# ArduinoNano_LearningBot_5-14-18.net
KiCad netlist of a schematic drawn in EAGLE
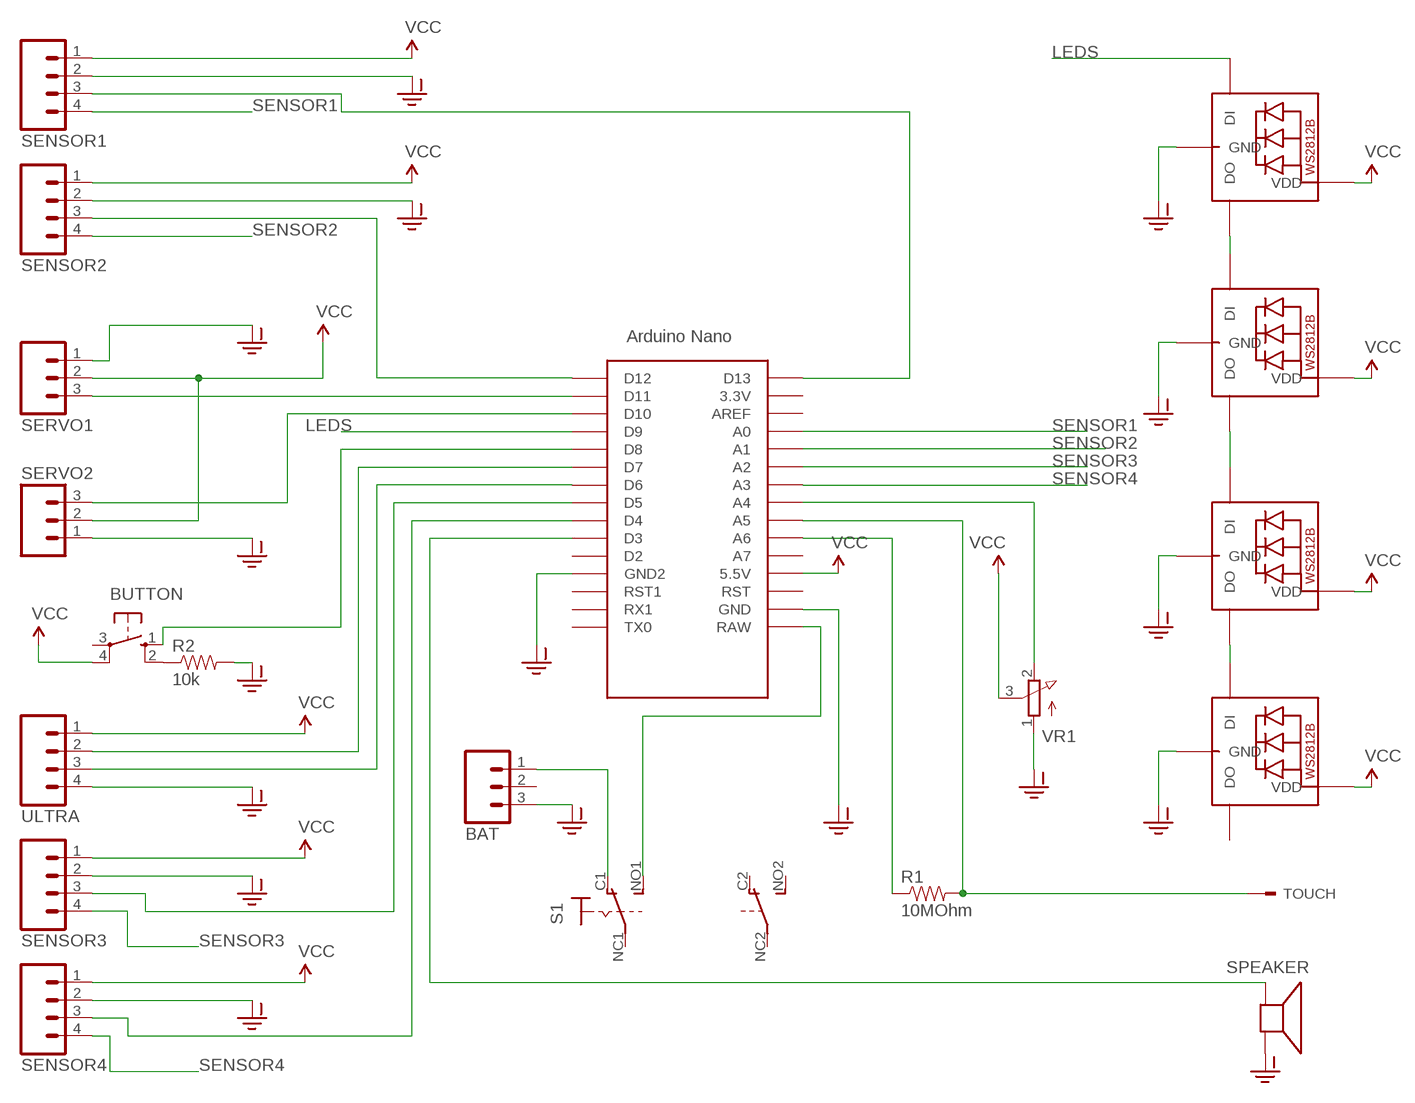
[diagram p0: schematic, sheet 1]

(export (version "E")
  (design (tool "Eeschema 10.0.6"))
  (components
    (comp (ref "BAT")
      (value "M03POLAR")
      (footprint "eagle-import:MOLEX-1X3")
      (libsource (lib "eagle-import") (part "M03POLAR"))
    )
    (comp (ref "BUTTON")
      (value "10-XX")
      (footprint "eagle-import:B3F-10XX")
      (fields (field (name "MPN") "B3F-1000"))
      (libsource (lib "eagle-import") (part "10-XX"))
    )
    (comp (ref "LED1")
      (value "WS2812B5050")
      (footprint "eagle-import:WS2812B")
      (libsource (lib "eagle-import") (part "WS2812B5050"))
    )
    (comp (ref "LED2")
      (value "WS2812B5050")
      (footprint "eagle-import:WS2812B")
      (libsource (lib "eagle-import") (part "WS2812B5050"))
    )
    (comp (ref "LED3")
      (value "WS2812B5050")
      (footprint "eagle-import:WS2812B")
      (libsource (lib "eagle-import") (part "WS2812B5050"))
    )
    (comp (ref "LED4")
      (value "WS2812B5050")
      (footprint "eagle-import:WS2812B")
      (libsource (lib "eagle-import") (part "WS2812B5050"))
    )
    (comp (ref "R1")
      (value "10MOhm")
      (footprint "eagle-import:AXIAL-0.4")
      (libsource (lib "eagle-import") (part "RESISTORPTH-1/4W"))
    )
    (comp (ref "R2")
      (value "10k")
      (footprint "eagle-import:AXIAL-0.4")
      (libsource (lib "eagle-import") (part "RESISTORPTH-1/4W"))
    )
    (comp (ref "S1")
      (value "SWITCH_320-938")
      (footprint "eagle-import:PS22F03")
      (libsource (lib "eagle-import") (part "SWITCH_320-938"))
    )
    (comp (ref "SENSOR1")
      (value "M04LOCK")
      (footprint "eagle-import:1X04_LOCK")
      (libsource (lib "eagle-import") (part "M04LOCK"))
    )
    (comp (ref "SENSOR2")
      (value "M04LOCK")
      (footprint "eagle-import:1X04_LOCK")
      (libsource (lib "eagle-import") (part "M04LOCK"))
    )
    (comp (ref "SENSOR3")
      (value "M04LOCK")
      (footprint "eagle-import:1X04_LOCK")
      (libsource (lib "eagle-import") (part "M04LOCK"))
    )
    (comp (ref "SENSOR4")
      (value "M04LOCK")
      (footprint "eagle-import:1X04_LOCK")
      (libsource (lib "eagle-import") (part "M04LOCK"))
    )
    (comp (ref "SERVO1")
      (value "M03LOCK")
      (footprint "eagle-import:1X03_LOCK")
      (libsource (lib "eagle-import") (part "SparkFun-Connectors_513_M03LOCK"))
    )
    (comp (ref "SERVO2")
      (value "M03LOCK")
      (footprint "eagle-import:1X03_LOCK")
      (libsource (lib "eagle-import") (part "SparkFun-Connectors_513_M03LOCK"))
    )
    (comp (ref "SPEAKER")
      (value "SPEAKER/AL60P")
      (footprint "eagle-import:AL60P")
      (libsource (lib "eagle-import") (part "SPEAKER/AL60P"))
    )
    (comp (ref "TOUCH")
      (value "TOUCHSENSOR")
      (footprint "eagle-import:TOUCH1")
      (libsource (lib "eagle-import") (part "TOUCHSENSOR"))
    )
    (comp (ref "U$1")
      (value "ARDUINO-CLONE_NANO")
      (footprint "eagle-import:ARDUINO-CLONE_NANO")
      (libsource (lib "eagle-import") (part "ARDUINO-CLONE_NANO"))
    )
    (comp (ref "ULTRA")
      (value "M04LOCK")
      (footprint "eagle-import:1X04_LOCK")
      (libsource (lib "eagle-import") (part "M04LOCK"))
    )
    (comp (ref "VR1")
      (value "3RP/1610N-VERTICAL")
      (footprint "eagle-import:3RP_1610N-VERTICAL")
      (libsource (lib "eagle-import") (part "3RP/1610N-VERTICAL"))
    )
  )
  (nets
    (net (code "1") (name "/LEDS") (class "Default")
      (node (ref "LED1") (pin "4-DIN") (pinfunction "DI_4-DIN") (pintype "input"))
      (node (ref "U$1") (pin "D9") (pinfunction "D9_D9") (pintype "bidirectional"))
    )
    (net (code "2") (name "/SENSOR1") (class "Default")
      (node (ref "SENSOR1") (pin "4") (pinfunction "4_4") (pintype "passive"))
      (node (ref "U$1") (pin "A0") (pinfunction "A0_A0") (pintype "bidirectional"))
    )
    (net (code "3") (name "/SENSOR2") (class "Default")
      (node (ref "SENSOR2") (pin "4") (pinfunction "4_4") (pintype "passive"))
      (node (ref "U$1") (pin "A1") (pinfunction "A1_A1") (pintype "bidirectional"))
    )
    (net (code "4") (name "/SENSOR3") (class "Default")
      (node (ref "SENSOR3") (pin "4") (pinfunction "4_4") (pintype "passive"))
      (node (ref "U$1") (pin "A2") (pinfunction "A2_A2") (pintype "bidirectional"))
    )
    (net (code "5") (name "/SENSOR4") (class "Default")
      (node (ref "SENSOR4") (pin "4") (pinfunction "4_4") (pintype "passive"))
      (node (ref "U$1") (pin "A3") (pinfunction "A3_A3") (pintype "bidirectional"))
    )
    (net (code "6") (name "GND-ISO") (class "Default")
      (node (ref "BAT") (pin "3") (pinfunction "3_3") (pintype "passive"))
      (node (ref "LED1") (pin "3-GND") (pinfunction "GND_3-GND") (pintype "power_in"))
      (node (ref "LED2") (pin "3-GND") (pinfunction "GND_3-GND") (pintype "power_in"))
      (node (ref "LED3") (pin "3-GND") (pinfunction "GND_3-GND") (pintype "power_in"))
      (node (ref "LED4") (pin "3-GND") (pinfunction "GND_3-GND") (pintype "power_in"))
      (node (ref "R2") (pin "P$2") (pinfunction "2_P$2") (pintype "passive"))
      (node (ref "SENSOR1") (pin "2") (pinfunction "2_2") (pintype "passive"))
      (node (ref "SENSOR2") (pin "2") (pinfunction "2_2") (pintype "passive"))
      (node (ref "SENSOR3") (pin "2") (pinfunction "2_2") (pintype "passive"))
      (node (ref "SENSOR4") (pin "2") (pinfunction "2_2") (pintype "passive"))
      (node (ref "SERVO1") (pin "1") (pinfunction "1_1") (pintype "passive"))
      (node (ref "SERVO2") (pin "1") (pinfunction "1_1") (pintype "passive"))
      (node (ref "SPEAKER") (pin "1") (pinfunction "+_1") (pintype "passive"))
      (node (ref "U$1") (pin "GND") (pinfunction "GND_GND") (pintype "bidirectional"))
      (node (ref "U$1") (pin "GND1") (pinfunction "GND2_GND1") (pintype "bidirectional"))
      (node (ref "ULTRA") (pin "4") (pinfunction "4_4") (pintype "passive"))
      (node (ref "VR1") (pin "1") (pinfunction "A_1") (pintype "passive"))
    )
    (net (code "7") (name "Net-(BUTTON-S)") (class "Default")
      (node (ref "BUTTON") (pin "1") (pinfunction "S_1") (pintype "passive"))
      (node (ref "U$1") (pin "D8") (pinfunction "D8_D8") (pintype "bidirectional"))
    )
    (net (code "8") (name "Net-(BUTTON-S1)") (class "Default")
      (node (ref "BUTTON") (pin "2") (pinfunction "S1_2") (pintype "passive"))
      (node (ref "R2") (pin "P$1") (pinfunction "1_P$1") (pintype "passive"))
    )
    (net (code "9") (name "Net-(LED1-DO)") (class "Default")
      (node (ref "LED1") (pin "2-DOUT") (pinfunction "DO_2-DOUT") (pintype "output"))
      (node (ref "LED2") (pin "4-DIN") (pinfunction "DI_4-DIN") (pintype "input"))
    )
    (net (code "10") (name "Net-(LED2-DO)") (class "Default")
      (node (ref "LED2") (pin "2-DOUT") (pinfunction "DO_2-DOUT") (pintype "output"))
      (node (ref "LED3") (pin "4-DIN") (pinfunction "DI_4-DIN") (pintype "input"))
    )
    (net (code "11") (name "Net-(LED3-DO)") (class "Default")
      (node (ref "LED3") (pin "2-DOUT") (pinfunction "DO_2-DOUT") (pintype "output"))
      (node (ref "LED4") (pin "4-DIN") (pinfunction "DI_4-DIN") (pintype "input"))
    )
    (net (code "12") (name "Net-(R1-1)") (class "Default")
      (node (ref "R1") (pin "P$1") (pinfunction "1_P$1") (pintype "passive"))
      (node (ref "U$1") (pin "A6") (pinfunction "A6_A6") (pintype "bidirectional"))
    )
    (net (code "13") (name "Net-(R1-2)") (class "Default")
      (node (ref "R1") (pin "P$2") (pinfunction "2_P$2") (pintype "passive"))
      (node (ref "TOUCH") (pin "P$1") (pinfunction "1_P$1") (pintype "passive"))
      (node (ref "U$1") (pin "A5") (pinfunction "A5_A5") (pintype "bidirectional"))
    )
    (net (code "14") (name "Net-(S1A-O)") (class "Default")
      (node (ref "BAT") (pin "1") (pinfunction "1_1") (pintype "passive"))
      (node (ref "S1") (pin "C1") (pinfunction "O_C1") (pintype "passive"))
    )
    (net (code "15") (name "Net-(S1A-S)") (class "Default")
      (node (ref "S1") (pin "NO1") (pinfunction "S_NO1") (pintype "passive"))
      (node (ref "U$1") (pin "RAW") (pinfunction "RAW_RAW") (pintype "bidirectional"))
    )
    (net (code "16") (name "Net-(SENSOR1-Pad3)") (class "Default")
      (node (ref "SENSOR1") (pin "3") (pinfunction "3_3") (pintype "passive"))
      (node (ref "U$1") (pin "D13") (pinfunction "D13_D13") (pintype "bidirectional"))
    )
    (net (code "17") (name "Net-(SENSOR2-Pad3)") (class "Default")
      (node (ref "SENSOR2") (pin "3") (pinfunction "3_3") (pintype "passive"))
      (node (ref "U$1") (pin "D12") (pinfunction "D12_D12") (pintype "bidirectional"))
    )
    (net (code "18") (name "Net-(SENSOR3-Pad3)") (class "Default")
      (node (ref "SENSOR3") (pin "3") (pinfunction "3_3") (pintype "passive"))
      (node (ref "U$1") (pin "D5") (pinfunction "D5_D5") (pintype "bidirectional"))
    )
    (net (code "19") (name "Net-(SENSOR4-Pad3)") (class "Default")
      (node (ref "SENSOR4") (pin "3") (pinfunction "3_3") (pintype "passive"))
      (node (ref "U$1") (pin "D4") (pinfunction "D4_D4") (pintype "bidirectional"))
    )
    (net (code "20") (name "Net-(SERVO1-Pad3)") (class "Default")
      (node (ref "SERVO1") (pin "3") (pinfunction "3_3") (pintype "passive"))
      (node (ref "U$1") (pin "D11") (pinfunction "D11_D11") (pintype "bidirectional"))
    )
    (net (code "21") (name "Net-(SERVO2-Pad3)") (class "Default")
      (node (ref "SERVO2") (pin "3") (pinfunction "3_3") (pintype "passive"))
      (node (ref "U$1") (pin "D10") (pinfunction "D10_D10") (pintype "bidirectional"))
    )
    (net (code "22") (name "Net-(SPEAKER--)") (class "Default")
      (node (ref "SPEAKER") (pin "2") (pinfunction "-_2") (pintype "passive"))
      (node (ref "U$1") (pin "D3") (pinfunction "D3_D3") (pintype "bidirectional"))
    )
    (net (code "23") (name "Net-(U$1-PadD6)") (class "Default")
      (node (ref "U$1") (pin "D6") (pinfunction "D6_D6") (pintype "bidirectional"))
      (node (ref "ULTRA") (pin "3") (pinfunction "3_3") (pintype "passive"))
    )
    (net (code "24") (name "Net-(U$1-PadD7)") (class "Default")
      (node (ref "U$1") (pin "D7") (pinfunction "D7_D7") (pintype "bidirectional"))
      (node (ref "ULTRA") (pin "2") (pinfunction "2_2") (pintype "passive"))
    )
    (net (code "25") (name "Net-(VR1-E)") (class "Default")
      (node (ref "U$1") (pin "A4") (pinfunction "A4_A4") (pintype "bidirectional"))
      (node (ref "VR1") (pin "2") (pinfunction "E_2") (pintype "passive"))
    )
    (net (code "26") (name "VCC") (class "Default")
      (node (ref "BUTTON") (pin "4") (pinfunction "P1_4") (pintype "passive"))
      (node (ref "LED1") (pin "1-VDD") (pinfunction "VDD_1-VDD") (pintype "power_in"))
      (node (ref "LED2") (pin "1-VDD") (pinfunction "VDD_1-VDD") (pintype "power_in"))
      (node (ref "LED3") (pin "1-VDD") (pinfunction "VDD_1-VDD") (pintype "power_in"))
      (node (ref "LED4") (pin "1-VDD") (pinfunction "VDD_1-VDD") (pintype "power_in"))
      (node (ref "SENSOR1") (pin "1") (pinfunction "1_1") (pintype "passive"))
      (node (ref "SENSOR2") (pin "1") (pinfunction "1_1") (pintype "passive"))
      (node (ref "SENSOR3") (pin "1") (pinfunction "1_1") (pintype "passive"))
      (node (ref "SENSOR4") (pin "1") (pinfunction "1_1") (pintype "passive"))
      (node (ref "SERVO1") (pin "2") (pinfunction "2_2") (pintype "passive"))
      (node (ref "SERVO2") (pin "2") (pinfunction "2_2") (pintype "passive"))
      (node (ref "U$1") (pin "5V") (pinfunction "5.5V_5V") (pintype "bidirectional"))
      (node (ref "ULTRA") (pin "1") (pinfunction "1_1") (pintype "passive"))
      (node (ref "VR1") (pin "3") (pinfunction "S_3") (pintype "passive"))
    )
    (net (code "27") (name "unconnected-(BAT-Pad2)") (class "Default")
      (node (ref "BAT") (pin "2") (pinfunction "2_2") (pintype "passive"))
    )
    (net (code "28") (name "unconnected-(BUTTON-P-Pad3)") (class "Default")
      (node (ref "BUTTON") (pin "3") (pinfunction "P_3") (pintype "passive"))
    )
    (net (code "29") (name "unconnected-(LED4-DO-Pad2-DOUT)") (class "Default")
      (node (ref "LED4") (pin "2-DOUT") (pinfunction "DO_2-DOUT") (pintype "output"))
    )
    (net (code "30") (name "unconnected-(S1A-P-PadNC1)") (class "Default")
      (node (ref "S1") (pin "NC1") (pinfunction "P_NC1") (pintype "passive"))
    )
    (net (code "31") (name "unconnected-(S1B-O-PadC2)") (class "Default")
      (node (ref "S1") (pin "C2") (pinfunction "O_C2") (pintype "passive"))
    )
    (net (code "32") (name "unconnected-(S1B-P-PadNC2)") (class "Default")
      (node (ref "S1") (pin "NC2") (pinfunction "P_NC2") (pintype "passive"))
    )
    (net (code "33") (name "unconnected-(S1B-S-PadNO2)") (class "Default")
      (node (ref "S1") (pin "NO2") (pinfunction "S_NO2") (pintype "passive"))
    )
    (net (code "34") (name "unconnected-(U$1-Pad3.3V)") (class "Default")
      (node (ref "U$1") (pin "3.3V") (pinfunction "3.3V_3.3V") (pintype "bidirectional"))
    )
    (net (code "35") (name "unconnected-(U$1-PadA7)") (class "Default")
      (node (ref "U$1") (pin "A7") (pinfunction "A7_A7") (pintype "bidirectional"))
    )
    (net (code "36") (name "unconnected-(U$1-PadAREF)") (class "Default")
      (node (ref "U$1") (pin "AREF") (pinfunction "AREF_AREF") (pintype "bidirectional"))
    )
    (net (code "37") (name "unconnected-(U$1-PadD2)") (class "Default")
      (node (ref "U$1") (pin "D2") (pinfunction "D2_D2") (pintype "bidirectional"))
    )
    (net (code "38") (name "unconnected-(U$1-PadRST)") (class "Default")
      (node (ref "U$1") (pin "RST") (pinfunction "RST_RST") (pintype "bidirectional"))
    )
    (net (code "39") (name "unconnected-(U$1-PadRST1)") (class "Default")
      (node (ref "U$1") (pin "RST1") (pinfunction "RST1_RST1") (pintype "bidirectional"))
    )
    (net (code "40") (name "unconnected-(U$1-PadRX1)") (class "Default")
      (node (ref "U$1") (pin "RX1") (pinfunction "RX1_RX1") (pintype "bidirectional"))
    )
    (net (code "41") (name "unconnected-(U$1-PadTX0)") (class "Default")
      (node (ref "U$1") (pin "TX0") (pinfunction "TX0_TX0") (pintype "bidirectional"))
    )
  )
)
